# SAO_Genie.net
KiCad netlist of a schematic drawn in EAGLE
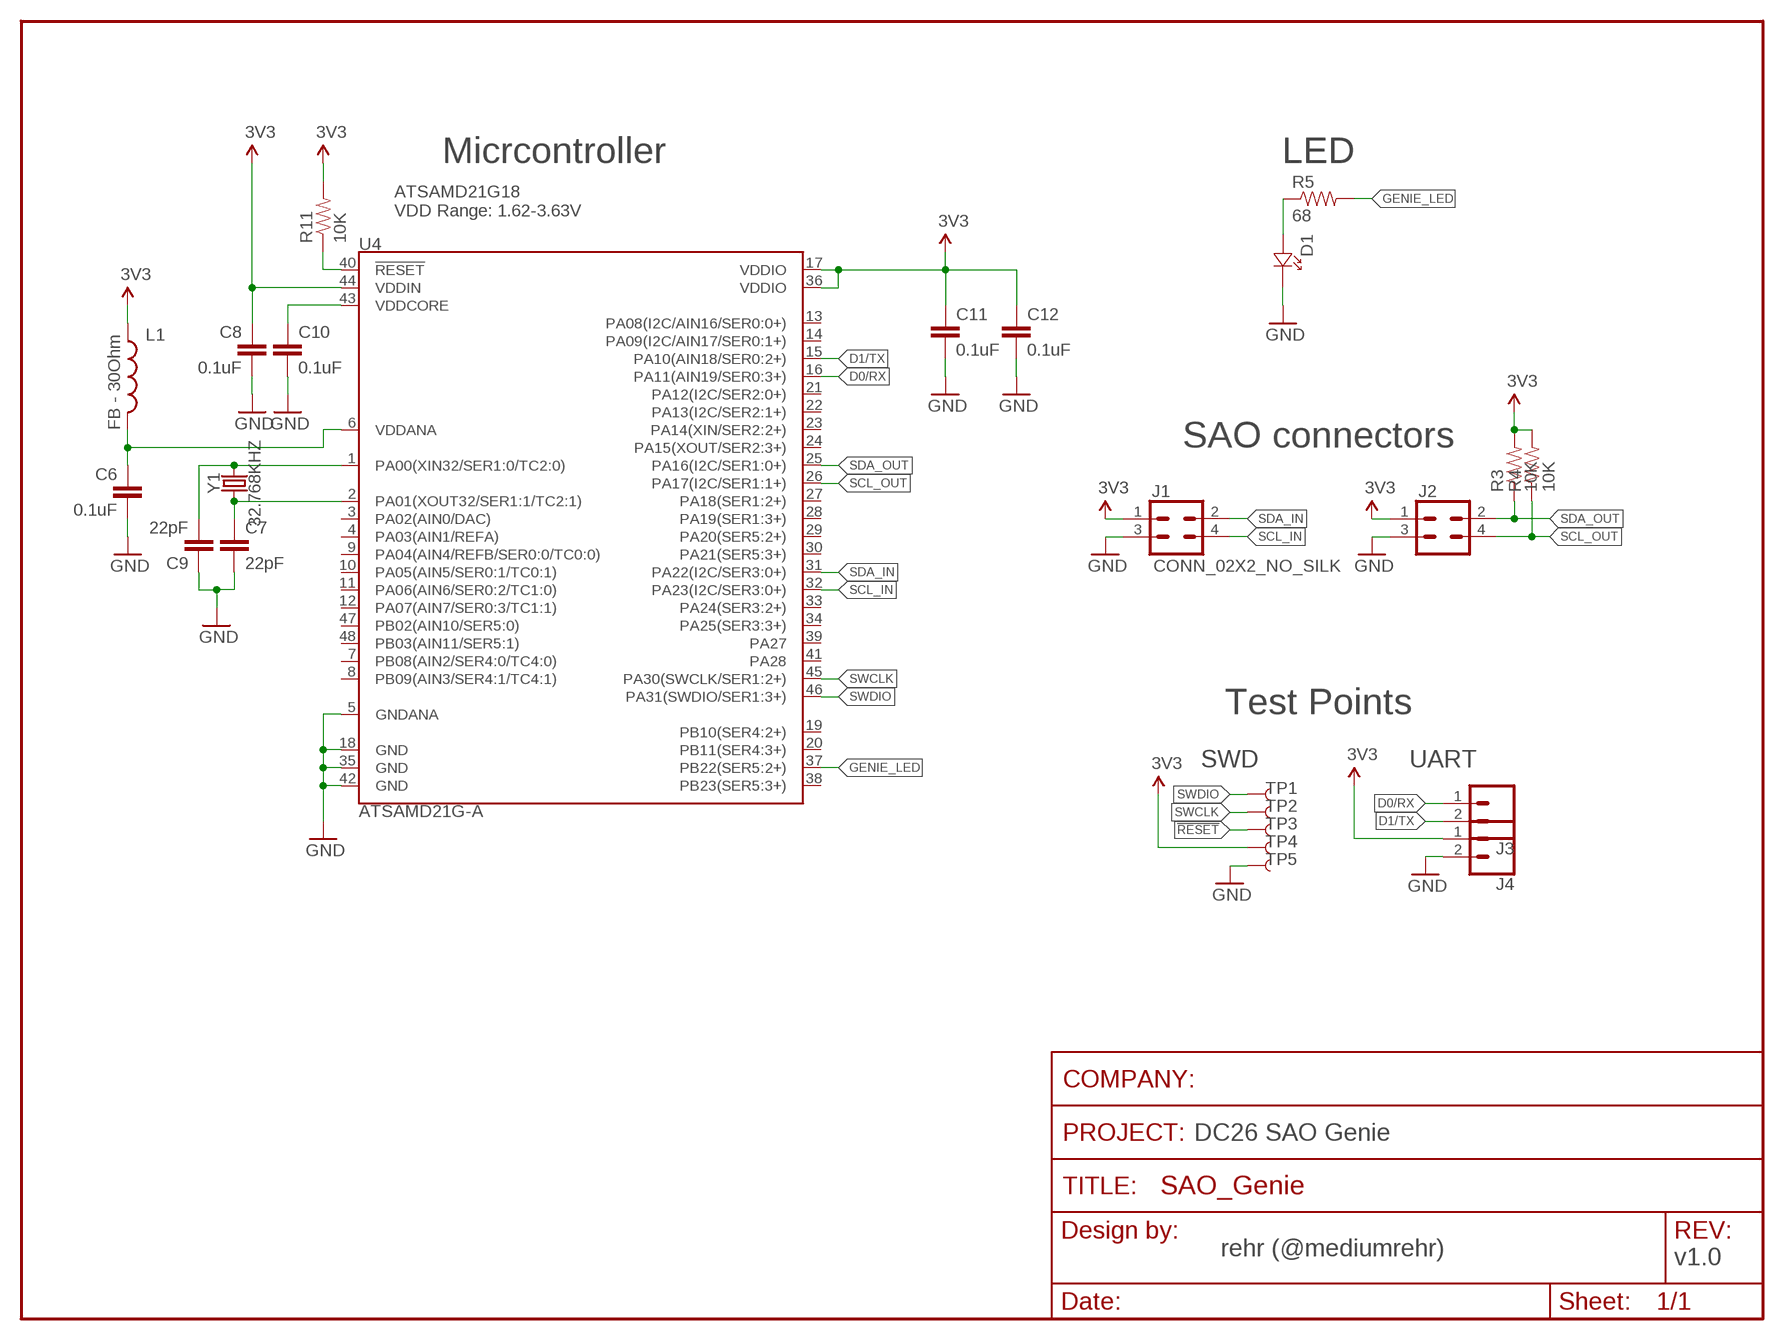
[diagram p0: schematic, sheet 1]

(export (version "E")
  (design (tool "Eeschema 10.0.6"))
  (components
    (comp (ref "C6")
      (value "0.1uF")
      (footprint "eagle-import:0603-CAP")
      (libsource (lib "eagle-import") (part "0.1UF-25V(+80/-20%)(0603)"))
    )
    (comp (ref "C7")
      (value "22pF")
      (footprint "eagle-import:0603-CAP")
      (libsource (lib "eagle-import") (part "15PF-50V-5%(0603)"))
    )
    (comp (ref "C8")
      (value "0.1uF")
      (footprint "eagle-import:0603-CAP")
      (libsource (lib "eagle-import") (part "0.1UF-25V(+80/-20%)(0603)"))
    )
    (comp (ref "C9")
      (value "22pF")
      (footprint "eagle-import:0603-CAP")
      (libsource (lib "eagle-import") (part "15PF-50V-5%(0603)"))
    )
    (comp (ref "C10")
      (value "0.1uF")
      (footprint "eagle-import:0603-CAP")
      (libsource (lib "eagle-import") (part "0.1UF-25V(+80/-20%)(0603)"))
    )
    (comp (ref "C11")
      (value "0.1uF")
      (footprint "eagle-import:0603-CAP")
      (libsource (lib "eagle-import") (part "0.1UF-25V(+80/-20%)(0603)"))
    )
    (comp (ref "C12")
      (value "0.1uF")
      (footprint "eagle-import:0603-CAP")
      (libsource (lib "eagle-import") (part "0.1UF-25V(+80/-20%)(0603)"))
    )
    (comp (ref "D1")
      (value "LED1206REVERSE_NO_SILK")
      (footprint "eagle-import:1206_NO_SILK")
      (libsource (lib "eagle-import") (part "LED1206REVERSE_NO_SILK"))
    )
    (comp (ref "FRAME1")
      (value "FRAME-LETTER-BLANKNO_PACKAGE")
      (footprint "eagle-import:DUMMY")
      (fields (field (name "DESIGNER") "Nobody"))
      (libsource (lib "eagle-import") (part "FRAME-LETTER-BLANKNO_PACKAGE"))
    )
    (comp (ref "J1")
      (value "CONN_02X2_NO_SILK")
      (footprint "eagle-import:2X2_NO_SILK")
      (libsource (lib "eagle-import") (part "CONN_02X2_NO_SILK"))
    )
    (comp (ref "J2")
      (value "SAO OUT")
      (footprint "eagle-import:2X2_NO_SILK")
      (libsource (lib "eagle-import") (part "CONN_02X2_NO_SILK"))
    )
    (comp (ref "J3")
      (value "CONN_021X02_NO_SILK")
      (footprint "eagle-import:1X02_NO_SILK")
      (libsource (lib "eagle-import") (part "CONN_021X02_NO_SILK"))
    )
    (comp (ref "J4")
      (value "CONN_021X02_NO_SILK")
      (footprint "eagle-import:1X02_NO_SILK")
      (libsource (lib "eagle-import") (part "CONN_021X02_NO_SILK"))
    )
    (comp (ref "L1")
      (value "FB - 30Ohm")
      (footprint "eagle-import:0603")
      (libsource (lib "eagle-import") (part "INDUCTOR0603"))
    )
    (comp (ref "R3")
      (value "10K")
      (footprint "eagle-import:0603-RES")
      (libsource (lib "eagle-import") (part "10KOHM-1/10W-1%(0603)0603"))
    )
    (comp (ref "R4")
      (value "10K")
      (footprint "eagle-import:0603-RES")
      (libsource (lib "eagle-import") (part "10KOHM-1/10W-1%(0603)0603"))
    )
    (comp (ref "R5")
      (value "68")
      (footprint "eagle-import:0603-RES")
      (libsource (lib "eagle-import") (part "10KOHM-1/10W-1%(0603)0603"))
    )
    (comp (ref "R11")
      (value "10K")
      (footprint "eagle-import:0603-RES")
      (libsource (lib "eagle-import") (part "10KOHM-1/10W-1%(0603)0603"))
    )
    (comp (ref "TP1")
      (value "TEST-POINT3X5")
      (footprint "eagle-import:PAD.03X.05")
      (libsource (lib "eagle-import") (part "TEST-POINT3X5"))
    )
    (comp (ref "TP2")
      (value "TEST-POINT3X5")
      (footprint "eagle-import:PAD.03X.05")
      (libsource (lib "eagle-import") (part "TEST-POINT3X5"))
    )
    (comp (ref "TP3")
      (value "TEST-POINT3X5")
      (footprint "eagle-import:PAD.03X.05")
      (libsource (lib "eagle-import") (part "TEST-POINT3X5"))
    )
    (comp (ref "TP4")
      (value "TEST-POINT3X5")
      (footprint "eagle-import:PAD.03X.05")
      (libsource (lib "eagle-import") (part "TEST-POINT3X5"))
    )
    (comp (ref "TP5")
      (value "TEST-POINT3X5")
      (footprint "eagle-import:PAD.03X.05")
      (libsource (lib "eagle-import") (part "TEST-POINT3X5"))
    )
    (comp (ref "U4")
      (value "ATSAMD21G-A")
      (footprint "eagle-import:TQFP-48")
      (libsource (lib "eagle-import") (part "ATSAMD21G-A"))
    )
    (comp (ref "Y1")
      (value "32.768KHZ")
      (footprint "eagle-import:ABS06")
      (libsource (lib "eagle-import") (part "ABS06-127-32.768KHZ"))
    )
  )
  (nets
    (net (code "1") (name "/~{RESET}") (class "Default")
      (node (ref "R11") (pin "1") (pinfunction "1_1") (pintype "passive"))
      (node (ref "TP3") (pin "P$1") (pinfunction "1_P$1") (pintype "bidirectional"))
      (node (ref "U4") (pin "40") (pinfunction "~{RESET}_40") (pintype "bidirectional"))
    )
    (net (code "2") (name "3V3") (class "Default")
      (node (ref "C11") (pin "1") (pinfunction "1_1") (pintype "passive"))
      (node (ref "C12") (pin "1") (pinfunction "1_1") (pintype "passive"))
      (node (ref "C8") (pin "1") (pinfunction "1_1") (pintype "passive"))
      (node (ref "J1") (pin "1") (pinfunction "1_1") (pintype "bidirectional"))
      (node (ref "J2") (pin "1") (pinfunction "1_1") (pintype "bidirectional"))
      (node (ref "J4") (pin "1") (pinfunction "1_1") (pintype "passive"))
      (node (ref "L1") (pin "1") (pinfunction "1_1") (pintype "passive"))
      (node (ref "R11") (pin "2") (pinfunction "2_2") (pintype "passive"))
      (node (ref "R3") (pin "2") (pinfunction "2_2") (pintype "passive"))
      (node (ref "R4") (pin "2") (pinfunction "2_2") (pintype "passive"))
      (node (ref "TP4") (pin "P$1") (pinfunction "1_P$1") (pintype "bidirectional"))
      (node (ref "U4") (pin "17") (pinfunction "VDDIO_17") (pintype "bidirectional"))
      (node (ref "U4") (pin "36") (pinfunction "VDDIO_36") (pintype "bidirectional"))
      (node (ref "U4") (pin "44") (pinfunction "VDDIN_44") (pintype "bidirectional"))
    )
    (net (code "3") (name "D0{slash}RX") (class "Default")
      (node (ref "J3") (pin "1") (pinfunction "1_1") (pintype "passive"))
      (node (ref "U4") (pin "16") (pinfunction "PA11(AIN19/SER0:3+)_16") (pintype "bidirectional"))
    )
    (net (code "4") (name "D1{slash}TX") (class "Default")
      (node (ref "J3") (pin "2") (pinfunction "2_2") (pintype "passive"))
      (node (ref "U4") (pin "15") (pinfunction "PA10(AIN18/SER0:2+)_15") (pintype "bidirectional"))
    )
    (net (code "5") (name "GENIE_LED") (class "Default")
      (node (ref "R5") (pin "2") (pinfunction "2_2") (pintype "passive"))
      (node (ref "U4") (pin "37") (pinfunction "PB22(SER5:2+)_37") (pintype "bidirectional"))
    )
    (net (code "6") (name "GND") (class "Default")
      (node (ref "C10") (pin "2") (pinfunction "2_2") (pintype "passive"))
      (node (ref "C11") (pin "2") (pinfunction "2_2") (pintype "passive"))
      (node (ref "C12") (pin "2") (pinfunction "2_2") (pintype "passive"))
      (node (ref "C6") (pin "2") (pinfunction "2_2") (pintype "passive"))
      (node (ref "C7") (pin "2") (pinfunction "2_2") (pintype "passive"))
      (node (ref "C8") (pin "2") (pinfunction "2_2") (pintype "passive"))
      (node (ref "C9") (pin "1") (pinfunction "1_1") (pintype "passive"))
      (node (ref "D1") (pin "P$1") (pinfunction "P$2_P$1") (pintype "bidirectional"))
      (node (ref "J1") (pin "3") (pinfunction "3_3") (pintype "bidirectional"))
      (node (ref "J2") (pin "3") (pinfunction "3_3") (pintype "bidirectional"))
      (node (ref "J4") (pin "2") (pinfunction "2_2") (pintype "passive"))
      (node (ref "TP5") (pin "P$1") (pinfunction "1_P$1") (pintype "bidirectional"))
      (node (ref "U4") (pin "18") (pinfunction "GND_18") (pintype "bidirectional"))
      (node (ref "U4") (pin "35") (pinfunction "GND_35") (pintype "bidirectional"))
      (node (ref "U4") (pin "42") (pinfunction "GND_42") (pintype "bidirectional"))
      (node (ref "U4") (pin "5") (pinfunction "GNDANA_5") (pintype "bidirectional"))
    )
    (net (code "7") (name "Net-(D1-P$1)") (class "Default")
      (node (ref "D1") (pin "P$2") (pinfunction "P$1_P$2") (pintype "bidirectional"))
      (node (ref "R5") (pin "1") (pinfunction "1_1") (pintype "passive"))
    )
    (net (code "8") (name "Net-(U4-PA00(XIN32{slash}SER1:0{slash}TC2:0))") (class "Default")
      (node (ref "C9") (pin "2") (pinfunction "2_2") (pintype "passive"))
      (node (ref "U4") (pin "1") (pinfunction "PA00(XIN32/SER1:0/TC2:0)_1") (pintype "bidirectional"))
      (node (ref "Y1") (pin "P$2") (pinfunction "2_P$2") (pintype "passive"))
    )
    (net (code "9") (name "Net-(U4-PA01(XOUT32{slash}SER1:1{slash}TC2:1))") (class "Default")
      (node (ref "C7") (pin "1") (pinfunction "1_1") (pintype "passive"))
      (node (ref "U4") (pin "2") (pinfunction "PA01(XOUT32/SER1:1/TC2:1)_2") (pintype "bidirectional"))
      (node (ref "Y1") (pin "P$1") (pinfunction "1_P$1") (pintype "passive"))
    )
    (net (code "10") (name "Net-(U4-VDDANA)") (class "Default")
      (node (ref "C6") (pin "1") (pinfunction "1_1") (pintype "passive"))
      (node (ref "L1") (pin "2") (pinfunction "2_2") (pintype "passive"))
      (node (ref "U4") (pin "6") (pinfunction "VDDANA_6") (pintype "bidirectional"))
    )
    (net (code "11") (name "Net-(U4-VDDCORE)") (class "Default")
      (node (ref "C10") (pin "1") (pinfunction "1_1") (pintype "passive"))
      (node (ref "U4") (pin "43") (pinfunction "VDDCORE_43") (pintype "bidirectional"))
    )
    (net (code "12") (name "SCL_IN") (class "Default")
      (node (ref "J1") (pin "4") (pinfunction "4_4") (pintype "bidirectional"))
      (node (ref "U4") (pin "32") (pinfunction "PA23(I2C/SER3:0+)_32") (pintype "bidirectional"))
    )
    (net (code "13") (name "SCL_OUT") (class "Default")
      (node (ref "J2") (pin "4") (pinfunction "4_4") (pintype "bidirectional"))
      (node (ref "R4") (pin "1") (pinfunction "1_1") (pintype "passive"))
      (node (ref "U4") (pin "26") (pinfunction "PA17(I2C/SER1:1+)_26") (pintype "bidirectional"))
    )
    (net (code "14") (name "SDA_IN") (class "Default")
      (node (ref "J1") (pin "2") (pinfunction "2_2") (pintype "bidirectional"))
      (node (ref "U4") (pin "31") (pinfunction "PA22(I2C/SER3:0+)_31") (pintype "bidirectional"))
    )
    (net (code "15") (name "SDA_OUT") (class "Default")
      (node (ref "J2") (pin "2") (pinfunction "2_2") (pintype "bidirectional"))
      (node (ref "R3") (pin "1") (pinfunction "1_1") (pintype "passive"))
      (node (ref "U4") (pin "25") (pinfunction "PA16(I2C/SER1:0+)_25") (pintype "bidirectional"))
    )
    (net (code "16") (name "SWCLK") (class "Default")
      (node (ref "TP2") (pin "P$1") (pinfunction "1_P$1") (pintype "bidirectional"))
      (node (ref "U4") (pin "45") (pinfunction "PA30(SWCLK/SER1:2+)_45") (pintype "bidirectional"))
    )
    (net (code "17") (name "SWDIO") (class "Default")
      (node (ref "TP1") (pin "P$1") (pinfunction "1_P$1") (pintype "bidirectional"))
      (node (ref "U4") (pin "46") (pinfunction "PA31(SWDIO/SER1:3+)_46") (pintype "bidirectional"))
    )
    (net (code "18") (name "unconnected-(U4-PA02(AIN0{slash}DAC)-Pad3)") (class "Default")
      (node (ref "U4") (pin "3") (pinfunction "PA02(AIN0/DAC)_3") (pintype "bidirectional"))
    )
    (net (code "19") (name "unconnected-(U4-PA03(AIN1{slash}REFA)-Pad4)") (class "Default")
      (node (ref "U4") (pin "4") (pinfunction "PA03(AIN1/REFA)_4") (pintype "bidirectional"))
    )
    (net (code "20") (name "unconnected-(U4-PA04(AIN4{slash}REFB{slash}SER0:0{slash}TC0:0)-Pad9)") (class "Default")
      (node (ref "U4") (pin "9") (pinfunction "PA04(AIN4/REFB/SER0:0/TC0:0)_9") (pintype "bidirectional"))
    )
    (net (code "21") (name "unconnected-(U4-PA05(AIN5{slash}SER0:1{slash}TC0:1)-Pad10)") (class "Default")
      (node (ref "U4") (pin "10") (pinfunction "PA05(AIN5/SER0:1/TC0:1)_10") (pintype "bidirectional"))
    )
    (net (code "22") (name "unconnected-(U4-PA06(AIN6{slash}SER0:2{slash}TC1:0)-Pad11)") (class "Default")
      (node (ref "U4") (pin "11") (pinfunction "PA06(AIN6/SER0:2/TC1:0)_11") (pintype "bidirectional"))
    )
    (net (code "23") (name "unconnected-(U4-PA07(AIN7{slash}SER0:3{slash}TC1:1)-Pad12)") (class "Default")
      (node (ref "U4") (pin "12") (pinfunction "PA07(AIN7/SER0:3/TC1:1)_12") (pintype "bidirectional"))
    )
    (net (code "24") (name "unconnected-(U4-PA08(I2C{slash}AIN16{slash}SER0:0+)-Pad13)") (class "Default")
      (node (ref "U4") (pin "13") (pinfunction "PA08(I2C/AIN16/SER0:0+)_13") (pintype "bidirectional"))
    )
    (net (code "25") (name "unconnected-(U4-PA09(I2C{slash}AIN17{slash}SER0:1+)-Pad14)") (class "Default")
      (node (ref "U4") (pin "14") (pinfunction "PA09(I2C/AIN17/SER0:1+)_14") (pintype "bidirectional"))
    )
    (net (code "26") (name "unconnected-(U4-PA12(I2C{slash}SER2:0+)-Pad21)") (class "Default")
      (node (ref "U4") (pin "21") (pinfunction "PA12(I2C/SER2:0+)_21") (pintype "bidirectional"))
    )
    (net (code "27") (name "unconnected-(U4-PA13(I2C{slash}SER2:1+)-Pad22)") (class "Default")
      (node (ref "U4") (pin "22") (pinfunction "PA13(I2C/SER2:1+)_22") (pintype "bidirectional"))
    )
    (net (code "28") (name "unconnected-(U4-PA14(XIN{slash}SER2:2+)-Pad23)") (class "Default")
      (node (ref "U4") (pin "23") (pinfunction "PA14(XIN/SER2:2+)_23") (pintype "bidirectional"))
    )
    (net (code "29") (name "unconnected-(U4-PA15(XOUT{slash}SER2:3+)-Pad24)") (class "Default")
      (node (ref "U4") (pin "24") (pinfunction "PA15(XOUT/SER2:3+)_24") (pintype "bidirectional"))
    )
    (net (code "30") (name "unconnected-(U4-PA18(SER1:2+)-Pad27)") (class "Default")
      (node (ref "U4") (pin "27") (pinfunction "PA18(SER1:2+)_27") (pintype "bidirectional"))
    )
    (net (code "31") (name "unconnected-(U4-PA19(SER1:3+)-Pad28)") (class "Default")
      (node (ref "U4") (pin "28") (pinfunction "PA19(SER1:3+)_28") (pintype "bidirectional"))
    )
    (net (code "32") (name "unconnected-(U4-PA20(SER5:2+)-Pad29)") (class "Default")
      (node (ref "U4") (pin "29") (pinfunction "PA20(SER5:2+)_29") (pintype "bidirectional"))
    )
    (net (code "33") (name "unconnected-(U4-PA21(SER5:3+)-Pad30)") (class "Default")
      (node (ref "U4") (pin "30") (pinfunction "PA21(SER5:3+)_30") (pintype "bidirectional"))
    )
    (net (code "34") (name "unconnected-(U4-PA24(SER3:2+)-Pad33)") (class "Default")
      (node (ref "U4") (pin "33") (pinfunction "PA24(SER3:2+)_33") (pintype "bidirectional"))
    )
    (net (code "35") (name "unconnected-(U4-PA25(SER3:3+)-Pad34)") (class "Default")
      (node (ref "U4") (pin "34") (pinfunction "PA25(SER3:3+)_34") (pintype "bidirectional"))
    )
    (net (code "36") (name "unconnected-(U4-PA27-Pad39)") (class "Default")
      (node (ref "U4") (pin "39") (pinfunction "PA27_39") (pintype "bidirectional"))
    )
    (net (code "37") (name "unconnected-(U4-PA28-Pad41)") (class "Default")
      (node (ref "U4") (pin "41") (pinfunction "PA28_41") (pintype "bidirectional"))
    )
    (net (code "38") (name "unconnected-(U4-PB02(AIN10{slash}SER5:0)-Pad47)") (class "Default")
      (node (ref "U4") (pin "47") (pinfunction "PB02(AIN10/SER5:0)_47") (pintype "bidirectional"))
    )
    (net (code "39") (name "unconnected-(U4-PB03(AIN11{slash}SER5:1)-Pad48)") (class "Default")
      (node (ref "U4") (pin "48") (pinfunction "PB03(AIN11/SER5:1)_48") (pintype "bidirectional"))
    )
    (net (code "40") (name "unconnected-(U4-PB08(AIN2{slash}SER4:0{slash}TC4:0)-Pad7)") (class "Default")
      (node (ref "U4") (pin "7") (pinfunction "PB08(AIN2/SER4:0/TC4:0)_7") (pintype "bidirectional"))
    )
    (net (code "41") (name "unconnected-(U4-PB09(AIN3{slash}SER4:1{slash}TC4:1)-Pad8)") (class "Default")
      (node (ref "U4") (pin "8") (pinfunction "PB09(AIN3/SER4:1/TC4:1)_8") (pintype "bidirectional"))
    )
    (net (code "42") (name "unconnected-(U4-PB10(SER4:2+)-Pad19)") (class "Default")
      (node (ref "U4") (pin "19") (pinfunction "PB10(SER4:2+)_19") (pintype "bidirectional"))
    )
    (net (code "43") (name "unconnected-(U4-PB11(SER4:3+)-Pad20)") (class "Default")
      (node (ref "U4") (pin "20") (pinfunction "PB11(SER4:3+)_20") (pintype "bidirectional"))
    )
    (net (code "44") (name "unconnected-(U4-PB23(SER5:3+)-Pad38)") (class "Default")
      (node (ref "U4") (pin "38") (pinfunction "PB23(SER5:3+)_38") (pintype "bidirectional"))
    )
  )
)
